# Day10F206.net
KiCad netlist of a schematic drawn in Altium Designer
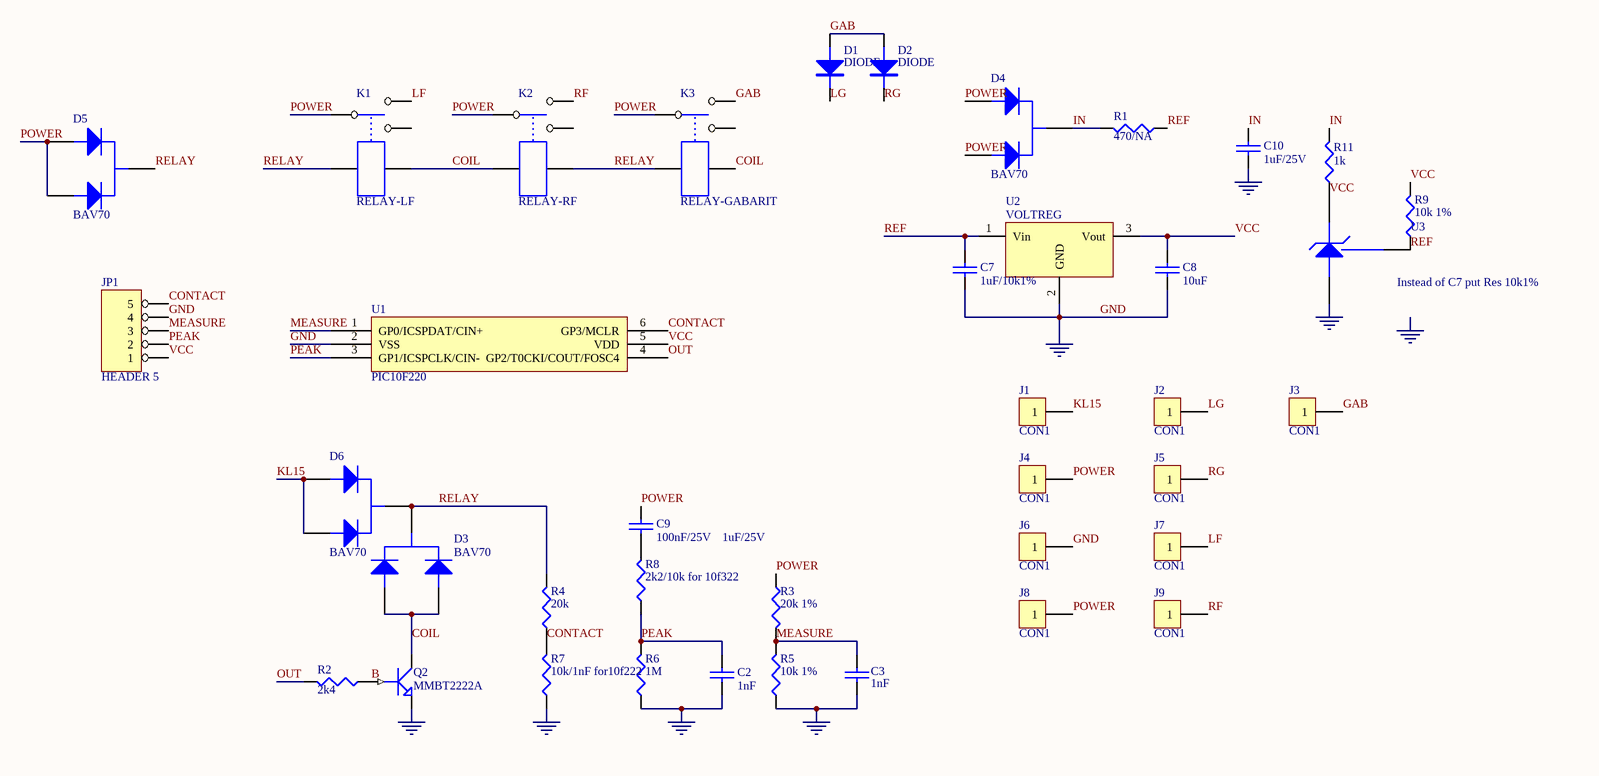
[diagram p0: Day10F206.SchDoc]

(export (version "E")
  (design (tool "Eeschema 10.0.6"))
  (components
    (comp (ref "C2")
      (value "1nF")
      (footprint "0603")
      (description "Capacitor")
      (libsource (lib "*") (part "CAP"))
    )
    (comp (ref "C3")
      (value "1nF")
      (footprint "0603")
      (description "Capacitor")
      (libsource (lib "*") (part "CAP"))
    )
    (comp (ref "C7")
      (value "1uF/10k1%")
      (footprint "0805")
      (description "Capacitor")
      (libsource (lib "*") (part "CAP"))
    )
    (comp (ref "C8")
      (value "10uF")
      (footprint "0805")
      (description "Capacitor")
      (libsource (lib "*") (part "CAP"))
    )
    (comp (ref "C9")
      (value "100nF/25V")
      (footprint "0603")
      (description "Capacitor")
      (libsource (lib "*") (part "CAP"))
    )
    (comp (ref "C10")
      (value "1uF/25V")
      (footprint "0805")
      (description "Capacitor")
      (libsource (lib "*") (part "CAP"))
    )
    (comp (ref "D1")
      (value "DIODE")
      (footprint "SMC")
      (description "Diode")
      (libsource (lib "Miscellaneous Devices") (part "DIODE"))
    )
    (comp (ref "D2")
      (value "DIODE")
      (footprint "SMC")
      (description "Diode")
      (libsource (lib "Miscellaneous Devices") (part "DIODE"))
    )
    (comp (ref "D3")
      (value "BAV70")
      (footprint "SOT-23")
      (libsource (lib "Devices") (part "DUAL DIODE BAV70"))
    )
    (comp (ref "D4")
      (value "BAV70")
      (footprint "SOT-23")
      (libsource (lib "Devices") (part "DUAL DIODE BAV70"))
    )
    (comp (ref "D5")
      (value "BAV70")
      (footprint "SOT-23")
      (libsource (lib "Devices") (part "DUAL DIODE BAV70"))
    )
    (comp (ref "D6")
      (value "BAV70")
      (footprint "SOT-23")
      (libsource (lib "Devices") (part "DUAL DIODE BAV70"))
    )
    (comp (ref "J1")
      (value "CON1")
      (footprint "SIP1 - WIRE")
      (description "Connector")
      (libsource (lib "Miscellaneous Devices") (part "CON1"))
    )
    (comp (ref "J2")
      (value "CON1")
      (footprint "SIP1 - WIRE")
      (description "Connector")
      (libsource (lib "Miscellaneous Devices") (part "CON1"))
    )
    (comp (ref "J3")
      (value "CON1")
      (footprint "SIP1 - WIRE")
      (description "Connector")
      (libsource (lib "Miscellaneous Devices") (part "CON1"))
    )
    (comp (ref "J4")
      (value "CON1")
      (footprint "SIP1 - WIRE")
      (description "Connector")
      (libsource (lib "Miscellaneous Devices") (part "CON1"))
    )
    (comp (ref "J5")
      (value "CON1")
      (footprint "SIP1 - WIRE")
      (description "Connector")
      (libsource (lib "Miscellaneous Devices") (part "CON1"))
    )
    (comp (ref "J6")
      (value "CON1")
      (footprint "SIP1 - WIRE")
      (description "Connector")
      (libsource (lib "Miscellaneous Devices") (part "CON1"))
    )
    (comp (ref "J7")
      (value "CON1")
      (footprint "SIP1 - WIRE")
      (description "Connector")
      (libsource (lib "Miscellaneous Devices") (part "CON1"))
    )
    (comp (ref "J8")
      (value "CON1")
      (footprint "SIP1 - WIRE")
      (description "Connector")
      (libsource (lib "Miscellaneous Devices") (part "CON1"))
    )
    (comp (ref "J9")
      (value "CON1")
      (footprint "SIP1 - WIRE")
      (description "Connector")
      (libsource (lib "Miscellaneous Devices") (part "CON1"))
    )
    (comp (ref "JP1")
      (value "HEADER 5")
      (footprint "SIP5 - PGM")
      (libsource (lib "Miscellaneous Devices") (part "HEADER 5"))
    )
    (comp (ref "K1")
      (value "RELAY-LF")
      (footprint "RELAY5PIN")
      (libsource (lib "Miscellaneous Devices") (part "RELAY-SPDT"))
    )
    (comp (ref "K2")
      (value "RELAY-RF")
      (footprint "RELAY5PIN")
      (libsource (lib "Miscellaneous Devices") (part "RELAY-SPDT"))
    )
    (comp (ref "K3")
      (value "RELAY-GABARIT")
      (footprint "RELAY5PIN")
      (libsource (lib "Miscellaneous Devices") (part "RELAY-SPDT"))
    )
    (comp (ref "Q2")
      (value "MMBT2222A")
      (footprint "SOT-23")
      (description "NPN Transistor")
      (libsource (lib "Miscellaneous Devices") (part "NPN1"))
    )
    (comp (ref "R1")
      (value "470/NA")
      (footprint "0603")
      (libsource (lib "Miscellaneous Devices") (part "RES1"))
    )
    (comp (ref "R2") (value "2k4") (footprint "0603") (libsource (lib "Miscellaneous Devices") (part "RES1")))
    (comp (ref "R3")
      (value "20k 1%")
      (footprint "0603")
      (libsource (lib "Miscellaneous Devices") (part "RES1"))
    )
    (comp (ref "R4") (value "20k") (footprint "0603") (libsource (lib "Miscellaneous Devices") (part "RES1")))
    (comp (ref "R5")
      (value "10k 1%")
      (footprint "0603")
      (libsource (lib "Miscellaneous Devices") (part "RES1"))
    )
    (comp (ref "R6") (value "1M") (footprint "0603") (libsource (lib "Miscellaneous Devices") (part "RES1")))
    (comp (ref "R7")
      (value "10k/1nF for10f222")
      (footprint "0603")
      (libsource (lib "Miscellaneous Devices") (part "RES1"))
    )
    (comp (ref "R8")
      (value "2k2/10k for 10f322")
      (footprint "0603")
      (libsource (lib "Miscellaneous Devices") (part "RES1"))
    )
    (comp (ref "R9")
      (value "10k 1%")
      (footprint "0603")
      (libsource (lib "Miscellaneous Devices") (part "RES1"))
    )
    (comp (ref "R11") (value "1k") (footprint "0603") (libsource (lib "Miscellaneous Devices") (part "RES1")))
    (comp (ref "U1") (value "PIC10F220") (footprint "SOT23 - 6") (libsource (lib "MCU") (part "PIC10F206")))
    (comp (ref "U2") (value "VOLTREG") (footprint "SO-8 VOLTREG") (libsource (lib "*") (part "VOLTREG")))
    (comp (ref "U3") (value "TL431") (footprint "SOT-23") (libsource (lib "Devices") (part "TL431")))
  )
  (nets
    (net (code "1") (name "/B") (class "Default")
      (node (ref "Q2") (pin "1") (pinfunction "B_1") (pintype "input"))
      (node (ref "R2") (pin "1") (pinfunction "1_1") (pintype "passive"))
    )
    (net (code "2") (name "/COIL") (class "Default")
      (node (ref "D3") (pin "1") (pinfunction "A1_1") (pintype "passive"))
      (node (ref "D3") (pin "3") (pinfunction "A2_3") (pintype "passive"))
      (node (ref "K1") (pin "5") (pinfunction "5_5") (pintype "passive"))
      (node (ref "K2") (pin "4") (pinfunction "4_4") (pintype "passive"))
      (node (ref "K3") (pin "5") (pinfunction "5_5") (pintype "passive"))
      (node (ref "Q2") (pin "2") (pinfunction "C_2") (pintype "passive"))
    )
    (net (code "3") (name "/CONTACT") (class "Default")
      (node (ref "JP1") (pin "5") (pinfunction "5_5") (pintype "passive"))
      (node (ref "R4") (pin "1") (pinfunction "1_1") (pintype "passive"))
      (node (ref "R7") (pin "2") (pinfunction "2_2") (pintype "passive"))
      (node (ref "U1") (pin "6") (pinfunction "GP3/MCLR_6") (pintype "passive"))
    )
    (net (code "4") (name "/GAB") (class "Default")
      (node (ref "D1") (pin "2") (pinfunction "A_2") (pintype "passive"))
      (node (ref "D2") (pin "2") (pinfunction "A_2") (pintype "passive"))
      (node (ref "J3") (pin "1") (pinfunction "1_1") (pintype "passive"))
      (node (ref "K3") (pin "2") (pinfunction "2_2") (pintype "passive"))
    )
    (net (code "5") (name "/IN") (class "Default")
      (node (ref "C10") (pin "1") (pinfunction "1_1") (pintype "passive"))
      (node (ref "D4") (pin "2") (pinfunction "K_2") (pintype "passive"))
      (node (ref "R1") (pin "2") (pinfunction "2_2") (pintype "passive"))
      (node (ref "R11") (pin "2") (pinfunction "2_2") (pintype "passive"))
    )
    (net (code "6") (name "/KL15") (class "Default")
      (node (ref "D6") (pin "1") (pinfunction "A1_1") (pintype "passive"))
      (node (ref "D6") (pin "3") (pinfunction "A2_3") (pintype "passive"))
      (node (ref "J1") (pin "1") (pinfunction "1_1") (pintype "passive"))
    )
    (net (code "7") (name "/LF") (class "Default")
      (node (ref "J7") (pin "1") (pinfunction "1_1") (pintype "passive"))
      (node (ref "K1") (pin "2") (pinfunction "2_2") (pintype "passive"))
    )
    (net (code "8") (name "/LG") (class "Default")
      (node (ref "D1") (pin "1") (pinfunction "K_1") (pintype "passive"))
      (node (ref "J2") (pin "1") (pinfunction "1_1") (pintype "passive"))
    )
    (net (code "9") (name "/MEASURE") (class "Default")
      (node (ref "C3") (pin "2") (pinfunction "2_2") (pintype "passive"))
      (node (ref "JP1") (pin "3") (pinfunction "3_3") (pintype "passive"))
      (node (ref "R3") (pin "2") (pinfunction "2_2") (pintype "passive"))
      (node (ref "R5") (pin "2") (pinfunction "2_2") (pintype "passive"))
      (node (ref "U1") (pin "1") (pinfunction "GP0/ICSPDAT/CIN+_1") (pintype "passive"))
    )
    (net (code "10") (name "/OUT") (class "Default")
      (node (ref "R2") (pin "2") (pinfunction "2_2") (pintype "passive"))
      (node (ref "U1") (pin "4") (pinfunction "GP2/T0CKI/COUT/FOSC4_4") (pintype "passive"))
    )
    (net (code "11") (name "/PEAK") (class "Default")
      (node (ref "C2") (pin "1") (pinfunction "1_1") (pintype "passive"))
      (node (ref "JP1") (pin "2") (pinfunction "2_2") (pintype "passive"))
      (node (ref "R6") (pin "2") (pinfunction "2_2") (pintype "passive"))
      (node (ref "R8") (pin "1") (pinfunction "1_1") (pintype "passive"))
      (node (ref "U1") (pin "3") (pinfunction "GP1/ICSPCLK/CIN-_3") (pintype "passive"))
    )
    (net (code "12") (name "/POWER") (class "Default")
      (node (ref "C9") (pin "1") (pinfunction "1_1") (pintype "passive"))
      (node (ref "D4") (pin "1") (pinfunction "A1_1") (pintype "passive"))
      (node (ref "D4") (pin "3") (pinfunction "A2_3") (pintype "passive"))
      (node (ref "D5") (pin "1") (pinfunction "A1_1") (pintype "passive"))
      (node (ref "D5") (pin "3") (pinfunction "A2_3") (pintype "passive"))
      (node (ref "J4") (pin "1") (pinfunction "1_1") (pintype "passive"))
      (node (ref "J8") (pin "1") (pinfunction "1_1") (pintype "passive"))
      (node (ref "K1") (pin "1") (pinfunction "1_1") (pintype "passive"))
      (node (ref "K2") (pin "1") (pinfunction "1_1") (pintype "passive"))
      (node (ref "K3") (pin "1") (pinfunction "1_1") (pintype "passive"))
      (node (ref "R3") (pin "1") (pinfunction "1_1") (pintype "passive"))
    )
    (net (code "13") (name "/REF") (class "Default")
      (node (ref "C7") (pin "1") (pinfunction "1_1") (pintype "passive"))
      (node (ref "R1") (pin "1") (pinfunction "1_1") (pintype "passive"))
      (node (ref "R9") (pin "1") (pinfunction "1_1") (pintype "passive"))
      (node (ref "U2") (pin "1") (pinfunction "Vin_1") (pintype "passive"))
      (node (ref "U3") (pin "1") (pinfunction "REF_1") (pintype "passive"))
    )
    (net (code "14") (name "/RELAY") (class "Default")
      (node (ref "D3") (pin "2") (pinfunction "K_2") (pintype "passive"))
      (node (ref "D5") (pin "2") (pinfunction "K_2") (pintype "passive"))
      (node (ref "D6") (pin "2") (pinfunction "K_2") (pintype "passive"))
      (node (ref "K1") (pin "4") (pinfunction "4_4") (pintype "passive"))
      (node (ref "K2") (pin "5") (pinfunction "5_5") (pintype "passive"))
      (node (ref "K3") (pin "4") (pinfunction "4_4") (pintype "passive"))
      (node (ref "R4") (pin "2") (pinfunction "2_2") (pintype "passive"))
    )
    (net (code "15") (name "/RF") (class "Default")
      (node (ref "J9") (pin "1") (pinfunction "1_1") (pintype "passive"))
      (node (ref "K2") (pin "2") (pinfunction "2_2") (pintype "passive"))
    )
    (net (code "16") (name "/RG") (class "Default")
      (node (ref "D2") (pin "1") (pinfunction "K_1") (pintype "passive"))
      (node (ref "J5") (pin "1") (pinfunction "1_1") (pintype "passive"))
    )
    (net (code "17") (name "/VCC") (class "Default")
      (node (ref "C8") (pin "1") (pinfunction "1_1") (pintype "passive"))
      (node (ref "JP1") (pin "1") (pinfunction "1_1") (pintype "passive"))
      (node (ref "R11") (pin "1") (pinfunction "1_1") (pintype "passive"))
      (node (ref "R9") (pin "2") (pinfunction "2_2") (pintype "passive"))
      (node (ref "U1") (pin "5") (pinfunction "VDD_5") (pintype "passive"))
      (node (ref "U2") (pin "3") (pinfunction "Vout_3") (pintype "passive"))
      (node (ref "U3") (pin "3") (pinfunction "K_3") (pintype "passive"))
    )
    (net (code "18") (name "GND") (class "Default")
      (node (ref "C10") (pin "2") (pinfunction "2_2") (pintype "passive"))
      (node (ref "C2") (pin "2") (pinfunction "2_2") (pintype "passive"))
      (node (ref "C3") (pin "1") (pinfunction "1_1") (pintype "passive"))
      (node (ref "C7") (pin "2") (pinfunction "2_2") (pintype "passive"))
      (node (ref "C8") (pin "2") (pinfunction "2_2") (pintype "passive"))
      (node (ref "J6") (pin "1") (pinfunction "1_1") (pintype "passive"))
      (node (ref "JP1") (pin "4") (pinfunction "4_4") (pintype "passive"))
      (node (ref "Q2") (pin "3") (pinfunction "E_3") (pintype "passive"))
      (node (ref "R5") (pin "1") (pinfunction "1_1") (pintype "passive"))
      (node (ref "R6") (pin "1") (pinfunction "1_1") (pintype "passive"))
      (node (ref "R7") (pin "1") (pinfunction "1_1") (pintype "passive"))
      (node (ref "U1") (pin "2") (pinfunction "VSS_2") (pintype "passive"))
      (node (ref "U2") (pin "2") (pinfunction "GND_2") (pintype "passive"))
      (node (ref "U3") (pin "2") (pinfunction "A_2") (pintype "passive"))
    )
    (net (code "19") (name "Net-(C9-Pad2)") (class "Default")
      (node (ref "C9") (pin "2") (pinfunction "2_2") (pintype "passive"))
      (node (ref "R8") (pin "2") (pinfunction "2_2") (pintype "passive"))
    )
    (net (code "20") (name "unconnected-(K1-Pad3)") (class "Default")
      (node (ref "K1") (pin "3") (pinfunction "3_3") (pintype "passive"))
    )
    (net (code "21") (name "unconnected-(K2-Pad3)") (class "Default")
      (node (ref "K2") (pin "3") (pinfunction "3_3") (pintype "passive"))
    )
    (net (code "22") (name "unconnected-(K3-Pad3)") (class "Default")
      (node (ref "K3") (pin "3") (pinfunction "3_3") (pintype "passive"))
    )
  )
)
